# relay.net
KiCad netlist of a schematic drawn in EAGLE
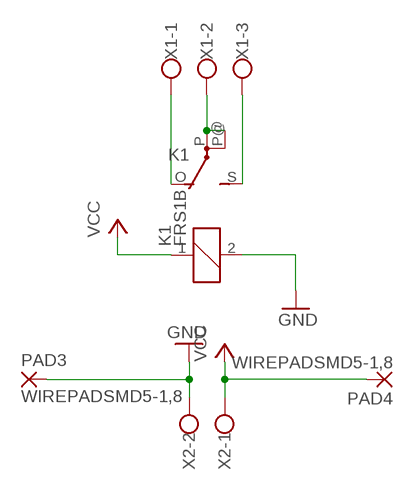
[diagram p0: schematic, sheet 1]
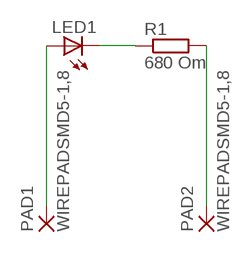
[diagram p1: schematic, sheet 2]

(export (version "E")
  (design (tool "Eeschema 10.0.6"))
  (components
    (comp (ref "LED1")
      (value "LED3MM")
      (footprint "eagle-import:LED3MM")
      (libsource (lib "eagle-import") (part "LED3MM"))
    )
    (comp (ref "PAD1")
      (value "WIREPADSMD5-1,8")
      (footprint "eagle-import:5-1,8")
      (libsource (lib "eagle-import") (part "WIREPADSMD5-1,8"))
    )
    (comp (ref "PAD2")
      (value "WIREPADSMD5-1,8")
      (footprint "eagle-import:5-1,8")
      (libsource (lib "eagle-import") (part "WIREPADSMD5-1,8"))
    )
    (comp (ref "R1")
      (value "680 Om")
      (footprint "eagle-import:0207_7")
      (libsource (lib "eagle-import") (part "R-EU_0207/7"))
    )
    (comp (ref "K1")
      (value "FRS1B")
      (footprint "eagle-import:FRS1B")
      (libsource (lib "eagle-import") (part "FRS1B"))
    )
    (comp (ref "PAD3")
      (value "WIREPADSMD5-1,8")
      (footprint "eagle-import:5-1,8")
      (libsource (lib "eagle-import") (part "WIREPADSMD5-1,8"))
    )
    (comp (ref "PAD4")
      (value "WIREPADSMD5-1,8")
      (footprint "eagle-import:5-1,8")
      (libsource (lib "eagle-import") (part "WIREPADSMD5-1,8"))
    )
    (comp (ref "X1")
      (value "W237-103")
      (footprint "eagle-import:W237-103")
      (fields (field (name "MPN") "237-103"))
      (libsource (lib "eagle-import") (part "W237-103"))
    )
    (comp (ref "X2")
      (value "W237-102")
      (footprint "eagle-import:W237-102")
      (fields (field (name "MPN") "237-102"))
      (libsource (lib "eagle-import") (part "W237-102"))
    )
  )
  (nets
    (net (code "1") (name "GND") (class "Default")
      (node (ref "K1") (pin "2") (pinfunction "2_2") (pintype "passive"))
      (node (ref "PAD3") (pin "1") (pinfunction "P_1") (pintype "passive"))
      (node (ref "X2") (pin "2") (pinfunction "KL_2") (pintype "passive"))
    )
    (net (code "2") (name "Net-(LED1-C)") (class "Default")
      (node (ref "LED1") (pin "K") (pinfunction "C_K") (pintype "passive"))
      (node (ref "R1") (pin "1") (pinfunction "1_1") (pintype "passive"))
    )
    (net (code "3") (name "Net-(PAD1-P)") (class "Default")
      (node (ref "LED1") (pin "A") (pinfunction "A_A") (pintype "passive"))
      (node (ref "PAD1") (pin "1") (pinfunction "P_1") (pintype "passive"))
    )
    (net (code "4") (name "Net-(PAD2-P)") (class "Default")
      (node (ref "PAD2") (pin "1") (pinfunction "P_1") (pintype "passive"))
      (node (ref "R1") (pin "2") (pinfunction "2_2") (pintype "passive"))
    )
    (net (code "5") (name "Net-(X1A-KL)") (class "Default")
      (node (ref "K1") (pin "O") (pinfunction "O_O") (pintype "passive"))
      (node (ref "X1") (pin "1") (pinfunction "KL_1") (pintype "passive"))
    )
    (net (code "6") (name "Net-(X1B-KL)") (class "Default")
      (node (ref "K1") (pin "P") (pinfunction "P_P") (pintype "passive"))
      (node (ref "K1") (pin "P@") (pinfunction "P_P@") (pintype "passive"))
      (node (ref "X1") (pin "2") (pinfunction "KL_2") (pintype "passive"))
    )
    (net (code "7") (name "Net-(X1C-KL)") (class "Default")
      (node (ref "K1") (pin "S") (pinfunction "S_S") (pintype "passive"))
      (node (ref "X1") (pin "3") (pinfunction "KL_3") (pintype "passive"))
    )
    (net (code "8") (name "VCC") (class "Default")
      (node (ref "K1") (pin "1") (pinfunction "1_1") (pintype "passive"))
      (node (ref "PAD4") (pin "1") (pinfunction "P_1") (pintype "passive"))
      (node (ref "X2") (pin "1") (pinfunction "KL_1") (pintype "passive"))
    )
  )
)
